# control_board_WS2812.net
KiCad netlist of a schematic drawn in EAGLE
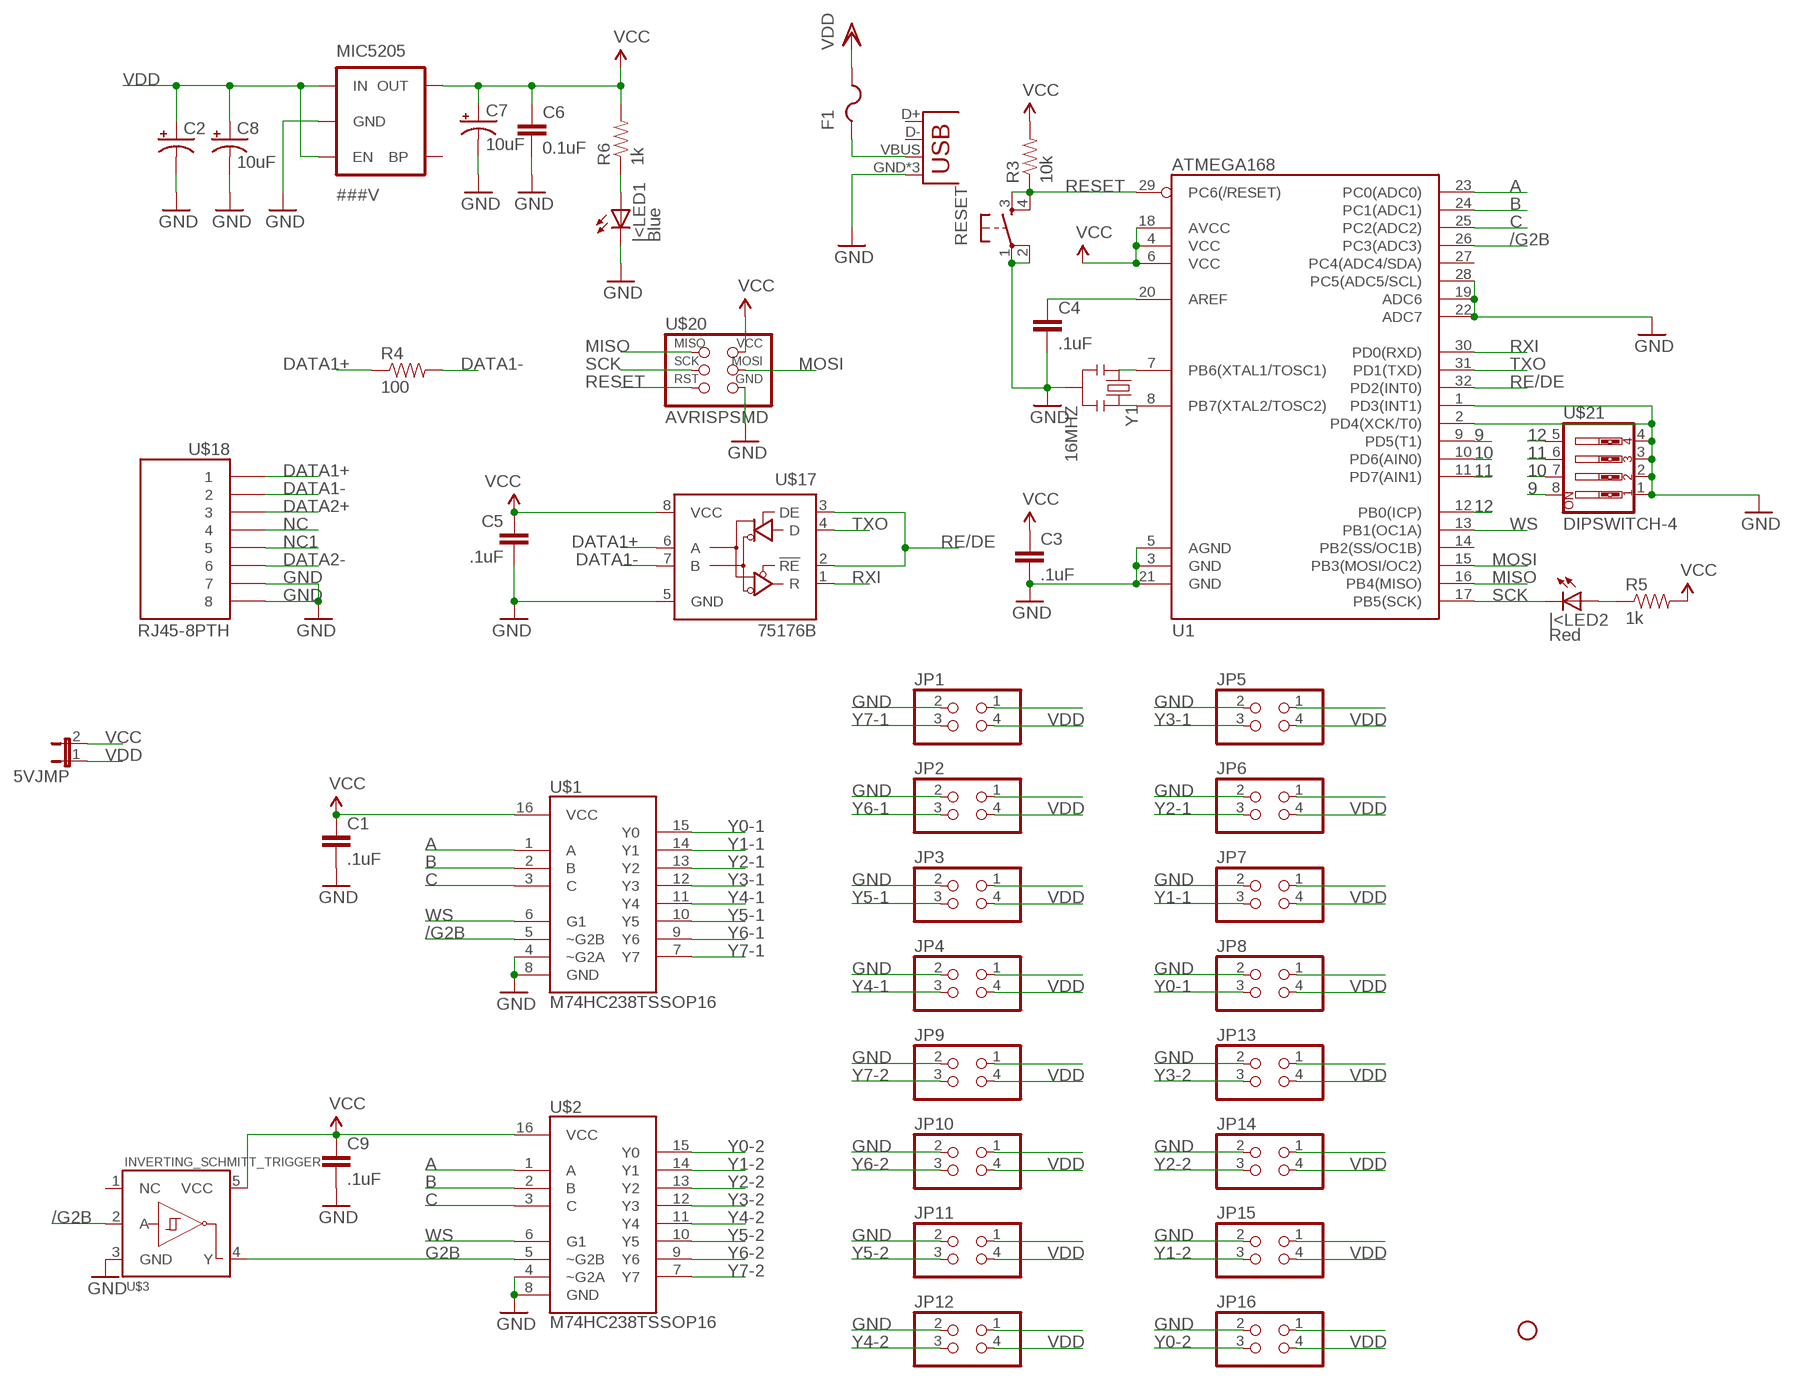
[diagram p0: schematic, sheet 1]

(export (version "E")
  (design (tool "Eeschema 10.0.6"))
  (components
    (comp (ref "5VJMP")
      (value "JUMPER-2SMD-NO")
      (footprint "eagle-import:SJ_2S-NO")
      (libsource (lib "eagle-import") (part "JUMPER-2SMD-NO"))
    )
    (comp (ref "C1")
      (value ".1uF")
      (footprint "eagle-import:0402-CAP")
      (libsource (lib "eagle-import") (part "CAP0402-CAP"))
    )
    (comp (ref "C2")
      (value "CAP_POLC")
      (footprint "eagle-import:PANASONIC_C")
      (libsource (lib "eagle-import") (part "CAP_POLC"))
    )
    (comp (ref "C3")
      (value ".1uF")
      (footprint "eagle-import:0402-CAP")
      (libsource (lib "eagle-import") (part "CAP0402-CAP"))
    )
    (comp (ref "C4")
      (value ".1uF")
      (footprint "eagle-import:0402-CAP")
      (libsource (lib "eagle-import") (part "CAP0402-CAP"))
    )
    (comp (ref "C5")
      (value ".1uF")
      (footprint "eagle-import:0402-CAP")
      (libsource (lib "eagle-import") (part "CAP0402-CAP"))
    )
    (comp (ref "C6")
      (value "0.1uF")
      (footprint "eagle-import:0402-CAP")
      (libsource (lib "eagle-import") (part "CAP0402-CAP"))
    )
    (comp (ref "C7")
      (value "10uF")
      (footprint "eagle-import:EIA3216")
      (libsource (lib "eagle-import") (part "CAP_POL1206"))
    )
    (comp (ref "C8")
      (value "10uF")
      (footprint "eagle-import:EIA3216")
      (libsource (lib "eagle-import") (part "CAP_POL1206"))
    )
    (comp (ref "C9")
      (value ".1uF")
      (footprint "eagle-import:0402-CAP")
      (libsource (lib "eagle-import") (part "CAP0402-CAP"))
    )
    (comp (ref "F1")
      (value "PTCFUSE-1812")
      (footprint "eagle-import:1812")
      (libsource (lib "eagle-import") (part "PTCFUSE-1812"))
    )
    (comp (ref "JP1")
      (value "PINHD-2X2")
      (footprint "eagle-import:2X02")
      (libsource (lib "eagle-import") (part "PINHD-2X2"))
    )
    (comp (ref "JP2")
      (value "PINHD-2X2")
      (footprint "eagle-import:2X02")
      (libsource (lib "eagle-import") (part "PINHD-2X2"))
    )
    (comp (ref "JP3")
      (value "PINHD-2X2")
      (footprint "eagle-import:2X02")
      (libsource (lib "eagle-import") (part "PINHD-2X2"))
    )
    (comp (ref "JP4")
      (value "PINHD-2X2")
      (footprint "eagle-import:2X02")
      (libsource (lib "eagle-import") (part "PINHD-2X2"))
    )
    (comp (ref "JP5")
      (value "PINHD-2X2")
      (footprint "eagle-import:2X02")
      (libsource (lib "eagle-import") (part "PINHD-2X2"))
    )
    (comp (ref "JP6")
      (value "PINHD-2X2")
      (footprint "eagle-import:2X02")
      (libsource (lib "eagle-import") (part "PINHD-2X2"))
    )
    (comp (ref "JP7")
      (value "PINHD-2X2")
      (footprint "eagle-import:2X02")
      (libsource (lib "eagle-import") (part "PINHD-2X2"))
    )
    (comp (ref "JP8")
      (value "PINHD-2X2")
      (footprint "eagle-import:2X02")
      (libsource (lib "eagle-import") (part "PINHD-2X2"))
    )
    (comp (ref "JP9")
      (value "PINHD-2X2")
      (footprint "eagle-import:2X02")
      (libsource (lib "eagle-import") (part "PINHD-2X2"))
    )
    (comp (ref "JP10")
      (value "PINHD-2X2")
      (footprint "eagle-import:2X02")
      (libsource (lib "eagle-import") (part "PINHD-2X2"))
    )
    (comp (ref "JP11")
      (value "PINHD-2X2")
      (footprint "eagle-import:2X02")
      (libsource (lib "eagle-import") (part "PINHD-2X2"))
    )
    (comp (ref "JP12")
      (value "PINHD-2X2")
      (footprint "eagle-import:2X02")
      (libsource (lib "eagle-import") (part "PINHD-2X2"))
    )
    (comp (ref "JP13")
      (value "PINHD-2X2")
      (footprint "eagle-import:2X02")
      (libsource (lib "eagle-import") (part "PINHD-2X2"))
    )
    (comp (ref "JP14")
      (value "PINHD-2X2")
      (footprint "eagle-import:2X02")
      (libsource (lib "eagle-import") (part "PINHD-2X2"))
    )
    (comp (ref "JP15")
      (value "PINHD-2X2")
      (footprint "eagle-import:2X02")
      (libsource (lib "eagle-import") (part "PINHD-2X2"))
    )
    (comp (ref "JP16")
      (value "PINHD-2X2")
      (footprint "eagle-import:2X02")
      (libsource (lib "eagle-import") (part "PINHD-2X2"))
    )
    (comp (ref "JP17")
      (value "USB-MICROB")
      (footprint "eagle-import:USB-MICROB")
      (libsource (lib "eagle-import") (part "USB-MICROB"))
    )
    (comp (ref "MIC5205")
      (value "###V")
      (footprint "eagle-import:SOT23-5")
      (libsource (lib "eagle-import") (part "V_REG_LDOSMD"))
    )
    (comp (ref "R3")
      (value "10k")
      (footprint "eagle-import:0402-RES")
      (libsource (lib "eagle-import") (part "RESISTOR0402-RES"))
    )
    (comp (ref "R4")
      (value "100")
      (footprint "eagle-import:1206")
      (libsource (lib "eagle-import") (part "SparkFun-Passives_RESISTOR1206"))
    )
    (comp (ref "R5")
      (value "1k")
      (footprint "eagle-import:C0402")
      (libsource (lib "eagle-import") (part "RESISTOR0402"))
    )
    (comp (ref "R6")
      (value "1k")
      (footprint "eagle-import:C0402")
      (libsource (lib "eagle-import") (part "RESISTOR0402"))
    )
    (comp (ref "RESET")
      (value "TAC_SWITCHSMD")
      (footprint "eagle-import:TACTILE_SWITCH_SMD")
      (libsource (lib "eagle-import") (part "TAC_SWITCHSMD"))
    )
    (comp (ref "STANDOFF1")
      (value "STAND-OFF")
      (footprint "eagle-import:STAND-OFF")
      (libsource (lib "eagle-import") (part "STAND-OFF"))
    )
    (comp (ref "U$1")
      (value "M74HC238TSSOP16")
      (footprint "eagle-import:TSSOP16")
      (libsource (lib "eagle-import") (part "M74HC238TSSOP16"))
    )
    (comp (ref "U$2")
      (value "M74HC238TSSOP16")
      (footprint "eagle-import:TSSOP16")
      (libsource (lib "eagle-import") (part "M74HC238TSSOP16"))
    )
    (comp (ref "U$3")
      (value "INVERTING_SCHMITT_TRIGGER")
      (footprint "eagle-import:TSSOP5")
      (libsource (lib "eagle-import") (part "INVERTING_SCHMITT_TRIGGER"))
    )
    (comp (ref "U$17")
      (value "75176B")
      (footprint "eagle-import:D_R-PDSO-G8")
      (libsource (lib "eagle-import") (part "75176B"))
    )
    (comp (ref "U$18")
      (value "RJ45-8PTH")
      (footprint "eagle-import:RJ45-8")
      (libsource (lib "eagle-import") (part "RJ45-8PTH"))
    )
    (comp (ref "U$20")
      (value "AVRISPSMD")
      (footprint "eagle-import:2X03SMD")
      (libsource (lib "eagle-import") (part "AVRISPSMD"))
    )
    (comp (ref "U$21")
      (value "DIPSWITCH-4")
      (footprint "eagle-import:DIPSWITCH-04")
      (libsource (lib "eagle-import") (part "DIPSWITCH-4"))
    )
    (comp (ref "U1")
      (value "ATMEGA168")
      (footprint "eagle-import:TQFP32-08")
      (libsource (lib "eagle-import") (part "ATMEGA168"))
    )
    (comp (ref "Y1")
      (value "16MHZ")
      (footprint "eagle-import:RESONATOR-SMD")
      (libsource (lib "eagle-import") (part "RESONATOR8MHZ"))
    )
    (comp (ref "|<LED1")
      (value "Blue")
      (footprint "eagle-import:LED-0603")
      (libsource (lib "eagle-import") (part "LED0603"))
    )
    (comp (ref "|<LED2")
      (value "Red")
      (footprint "eagle-import:LED-0603")
      (libsource (lib "eagle-import") (part "LED0603"))
    )
  )
  (nets
    (net (code "1") (name "/9") (class "Default")
      (node (ref "U$21") (pin "8") (pinfunction "8_8") (pintype "passive"))
      (node (ref "U1") (pin "9") (pinfunction "PD5(T1)_9") (pintype "bidirectional"))
    )
    (net (code "2") (name "/10") (class "Default")
      (node (ref "U$21") (pin "7") (pinfunction "7_7") (pintype "passive"))
      (node (ref "U1") (pin "10") (pinfunction "PD6(AIN0)_10") (pintype "bidirectional"))
    )
    (net (code "3") (name "/11") (class "Default")
      (node (ref "U$21") (pin "6") (pinfunction "6_6") (pintype "passive"))
      (node (ref "U1") (pin "11") (pinfunction "PD7(AIN1)_11") (pintype "bidirectional"))
    )
    (net (code "4") (name "/12") (class "Default")
      (node (ref "U$21") (pin "5") (pinfunction "5_5") (pintype "passive"))
      (node (ref "U1") (pin "12") (pinfunction "PB0(ICP)_12") (pintype "bidirectional"))
    )
    (net (code "5") (name "/A") (class "Default")
      (node (ref "U$1") (pin "1") (pinfunction "A_1") (pintype "bidirectional"))
      (node (ref "U$2") (pin "1") (pinfunction "A_1") (pintype "bidirectional"))
      (node (ref "U1") (pin "23") (pinfunction "PC0(ADC0)_23") (pintype "bidirectional"))
    )
    (net (code "6") (name "/B") (class "Default")
      (node (ref "U$1") (pin "2") (pinfunction "B_2") (pintype "bidirectional"))
      (node (ref "U$2") (pin "2") (pinfunction "B_2") (pintype "bidirectional"))
      (node (ref "U1") (pin "24") (pinfunction "PC1(ADC1)_24") (pintype "bidirectional"))
    )
    (net (code "7") (name "/C") (class "Default")
      (node (ref "U$1") (pin "3") (pinfunction "C_3") (pintype "bidirectional"))
      (node (ref "U$2") (pin "3") (pinfunction "C_3") (pintype "bidirectional"))
      (node (ref "U1") (pin "25") (pinfunction "PC2(ADC2)_25") (pintype "bidirectional"))
    )
    (net (code "8") (name "/DATA1+") (class "Default")
      (node (ref "R4") (pin "1") (pinfunction "1_1") (pintype "passive"))
      (node (ref "U$17") (pin "6") (pinfunction "A_6") (pintype "output"))
      (node (ref "U$18") (pin "1") (pinfunction "1_1") (pintype "bidirectional"))
    )
    (net (code "9") (name "/DATA1-") (class "Default")
      (node (ref "R4") (pin "2") (pinfunction "2_2") (pintype "passive"))
      (node (ref "U$17") (pin "7") (pinfunction "B_7") (pintype "output"))
      (node (ref "U$18") (pin "2") (pinfunction "2_2") (pintype "bidirectional"))
    )
    (net (code "10") (name "/DATA2+") (class "Default")
      (node (ref "U$18") (pin "3") (pinfunction "3_3") (pintype "bidirectional"))
    )
    (net (code "11") (name "/DATA2-") (class "Default")
      (node (ref "U$18") (pin "6") (pinfunction "6_6") (pintype "bidirectional"))
    )
    (net (code "12") (name "/G2B") (class "Default")
      (node (ref "U$2") (pin "5") (pinfunction "~{G2B}_5") (pintype "bidirectional"))
      (node (ref "U$3") (pin "4") (pinfunction "Y_4") (pintype "bidirectional"))
    )
    (net (code "13") (name "/MISO") (class "Default")
      (node (ref "U$20") (pin "1") (pinfunction "MISO_1") (pintype "passive"))
      (node (ref "U1") (pin "16") (pinfunction "PB4(MISO)_16") (pintype "bidirectional"))
    )
    (net (code "14") (name "/MOSI") (class "Default")
      (node (ref "U$20") (pin "4") (pinfunction "MOSI_4") (pintype "passive"))
      (node (ref "U1") (pin "15") (pinfunction "PB3(MOSI/OC2)_15") (pintype "bidirectional"))
    )
    (net (code "15") (name "/NC") (class "Default")
      (node (ref "U$18") (pin "4") (pinfunction "4_4") (pintype "bidirectional"))
    )
    (net (code "16") (name "/NC1") (class "Default")
      (node (ref "U$18") (pin "5") (pinfunction "5_5") (pintype "bidirectional"))
    )
    (net (code "17") (name "/RESET") (class "Default")
      (node (ref "R3") (pin "1") (pinfunction "1_1") (pintype "passive"))
      (node (ref "RESET") (pin "3") (pinfunction "3_3") (pintype "passive"))
      (node (ref "RESET") (pin "4") (pinfunction "4_4") (pintype "passive"))
      (node (ref "U$20") (pin "5") (pinfunction "RST_5") (pintype "passive"))
      (node (ref "U1") (pin "29") (pinfunction "PC6(/RESET)_29") (pintype "bidirectional"))
    )
    (net (code "18") (name "/RE{slash}DE") (class "Default")
      (node (ref "U$17") (pin "2") (pinfunction "~{RE}_2") (pintype "input"))
      (node (ref "U$17") (pin "3") (pinfunction "DE_3") (pintype "input"))
      (node (ref "U1") (pin "32") (pinfunction "PD2(INT0)_32") (pintype "bidirectional"))
    )
    (net (code "19") (name "/RXI") (class "Default")
      (node (ref "U$17") (pin "1") (pinfunction "R_1") (pintype "input"))
      (node (ref "U1") (pin "30") (pinfunction "PD0(RXD)_30") (pintype "bidirectional"))
    )
    (net (code "20") (name "/SCK") (class "Default")
      (node (ref "U$20") (pin "3") (pinfunction "SCK_3") (pintype "passive"))
      (node (ref "U1") (pin "17") (pinfunction "PB5(SCK)_17") (pintype "bidirectional"))
      (node (ref "|<LED2") (pin "C") (pinfunction "C_C") (pintype "passive"))
    )
    (net (code "21") (name "/TXO") (class "Default")
      (node (ref "U$17") (pin "4") (pinfunction "D_4") (pintype "input"))
      (node (ref "U1") (pin "31") (pinfunction "PD1(TXD)_31") (pintype "bidirectional"))
    )
    (net (code "22") (name "/WS") (class "Default")
      (node (ref "U$1") (pin "6") (pinfunction "G1_6") (pintype "bidirectional"))
      (node (ref "U$2") (pin "6") (pinfunction "G1_6") (pintype "bidirectional"))
      (node (ref "U1") (pin "13") (pinfunction "PB1(OC1A)_13") (pintype "bidirectional"))
    )
    (net (code "23") (name "/Y0-1") (class "Default")
      (node (ref "JP8") (pin "3") (pinfunction "3_3") (pintype "passive"))
      (node (ref "U$1") (pin "15") (pinfunction "Y0_15") (pintype "bidirectional"))
    )
    (net (code "24") (name "/Y0-2") (class "Default")
      (node (ref "JP16") (pin "3") (pinfunction "3_3") (pintype "passive"))
      (node (ref "U$2") (pin "15") (pinfunction "Y0_15") (pintype "bidirectional"))
    )
    (net (code "25") (name "/Y1-1") (class "Default")
      (node (ref "JP7") (pin "3") (pinfunction "3_3") (pintype "passive"))
      (node (ref "U$1") (pin "14") (pinfunction "Y1_14") (pintype "bidirectional"))
    )
    (net (code "26") (name "/Y1-2") (class "Default")
      (node (ref "JP15") (pin "3") (pinfunction "3_3") (pintype "passive"))
      (node (ref "U$2") (pin "14") (pinfunction "Y1_14") (pintype "bidirectional"))
    )
    (net (code "27") (name "/Y2-1") (class "Default")
      (node (ref "JP6") (pin "3") (pinfunction "3_3") (pintype "passive"))
      (node (ref "U$1") (pin "13") (pinfunction "Y2_13") (pintype "bidirectional"))
    )
    (net (code "28") (name "/Y2-2") (class "Default")
      (node (ref "JP14") (pin "3") (pinfunction "3_3") (pintype "passive"))
      (node (ref "U$2") (pin "13") (pinfunction "Y2_13") (pintype "bidirectional"))
    )
    (net (code "29") (name "/Y3-1") (class "Default")
      (node (ref "JP5") (pin "3") (pinfunction "3_3") (pintype "passive"))
      (node (ref "U$1") (pin "12") (pinfunction "Y3_12") (pintype "bidirectional"))
    )
    (net (code "30") (name "/Y3-2") (class "Default")
      (node (ref "JP13") (pin "3") (pinfunction "3_3") (pintype "passive"))
      (node (ref "U$2") (pin "12") (pinfunction "Y3_12") (pintype "bidirectional"))
    )
    (net (code "31") (name "/Y4-1") (class "Default")
      (node (ref "JP4") (pin "3") (pinfunction "3_3") (pintype "passive"))
      (node (ref "U$1") (pin "11") (pinfunction "Y4_11") (pintype "bidirectional"))
    )
    (net (code "32") (name "/Y4-2") (class "Default")
      (node (ref "JP12") (pin "3") (pinfunction "3_3") (pintype "passive"))
      (node (ref "U$2") (pin "11") (pinfunction "Y4_11") (pintype "bidirectional"))
    )
    (net (code "33") (name "/Y5-1") (class "Default")
      (node (ref "JP3") (pin "3") (pinfunction "3_3") (pintype "passive"))
      (node (ref "U$1") (pin "10") (pinfunction "Y5_10") (pintype "bidirectional"))
    )
    (net (code "34") (name "/Y5-2") (class "Default")
      (node (ref "JP11") (pin "3") (pinfunction "3_3") (pintype "passive"))
      (node (ref "U$2") (pin "10") (pinfunction "Y5_10") (pintype "bidirectional"))
    )
    (net (code "35") (name "/Y6-1") (class "Default")
      (node (ref "JP2") (pin "3") (pinfunction "3_3") (pintype "passive"))
      (node (ref "U$1") (pin "9") (pinfunction "Y6_9") (pintype "bidirectional"))
    )
    (net (code "36") (name "/Y6-2") (class "Default")
      (node (ref "JP10") (pin "3") (pinfunction "3_3") (pintype "passive"))
      (node (ref "U$2") (pin "9") (pinfunction "Y6_9") (pintype "bidirectional"))
    )
    (net (code "37") (name "/Y7-1") (class "Default")
      (node (ref "JP1") (pin "3") (pinfunction "3_3") (pintype "passive"))
      (node (ref "U$1") (pin "7") (pinfunction "Y7_7") (pintype "bidirectional"))
    )
    (net (code "38") (name "/Y7-2") (class "Default")
      (node (ref "JP9") (pin "3") (pinfunction "3_3") (pintype "passive"))
      (node (ref "U$2") (pin "7") (pinfunction "Y7_7") (pintype "bidirectional"))
    )
    (net (code "39") (name "/{slash}G2B") (class "Default")
      (node (ref "U$1") (pin "5") (pinfunction "~{G2B}_5") (pintype "bidirectional"))
      (node (ref "U$3") (pin "2") (pinfunction "A_2") (pintype "bidirectional"))
      (node (ref "U1") (pin "26") (pinfunction "PC3(ADC3)_26") (pintype "bidirectional"))
    )
    (net (code "40") (name "GND") (class "Default")
      (node (ref "C1") (pin "2") (pinfunction "2_2") (pintype "passive"))
      (node (ref "C2") (pin "-") (pinfunction "-_-") (pintype "passive"))
      (node (ref "C3") (pin "2") (pinfunction "2_2") (pintype "passive"))
      (node (ref "C4") (pin "2") (pinfunction "2_2") (pintype "passive"))
      (node (ref "C5") (pin "2") (pinfunction "2_2") (pintype "passive"))
      (node (ref "C6") (pin "2") (pinfunction "2_2") (pintype "passive"))
      (node (ref "C7") (pin "C") (pinfunction "-_C") (pintype "passive"))
      (node (ref "C8") (pin "C") (pinfunction "-_C") (pintype "passive"))
      (node (ref "C9") (pin "2") (pinfunction "2_2") (pintype "passive"))
      (node (ref "JP1") (pin "2") (pinfunction "2_2") (pintype "passive"))
      (node (ref "JP10") (pin "2") (pinfunction "2_2") (pintype "passive"))
      (node (ref "JP11") (pin "2") (pinfunction "2_2") (pintype "passive"))
      (node (ref "JP12") (pin "2") (pinfunction "2_2") (pintype "passive"))
      (node (ref "JP13") (pin "2") (pinfunction "2_2") (pintype "passive"))
      (node (ref "JP14") (pin "2") (pinfunction "2_2") (pintype "passive"))
      (node (ref "JP15") (pin "2") (pinfunction "2_2") (pintype "passive"))
      (node (ref "JP16") (pin "2") (pinfunction "2_2") (pintype "passive"))
      (node (ref "JP17") (pin "GND") (pinfunction "GND_GND") (pintype "bidirectional"))
      (node (ref "JP17") (pin "MT1") (pinfunction "GND_MT1") (pintype "bidirectional"))
      (node (ref "JP17") (pin "MT2") (pinfunction "GND_MT2") (pintype "bidirectional"))
      (node (ref "JP2") (pin "2") (pinfunction "2_2") (pintype "passive"))
      (node (ref "JP3") (pin "2") (pinfunction "2_2") (pintype "passive"))
      (node (ref "JP4") (pin "2") (pinfunction "2_2") (pintype "passive"))
      (node (ref "JP5") (pin "2") (pinfunction "2_2") (pintype "passive"))
      (node (ref "JP6") (pin "2") (pinfunction "2_2") (pintype "passive"))
      (node (ref "JP7") (pin "2") (pinfunction "2_2") (pintype "passive"))
      (node (ref "JP8") (pin "2") (pinfunction "2_2") (pintype "passive"))
      (node (ref "JP9") (pin "2") (pinfunction "2_2") (pintype "passive"))
      (node (ref "MIC5205") (pin "2") (pinfunction "GND_2") (pintype "input"))
      (node (ref "RESET") (pin "1") (pinfunction "1_1") (pintype "passive"))
      (node (ref "RESET") (pin "2") (pinfunction "2_2") (pintype "passive"))
      (node (ref "U$1") (pin "4") (pinfunction "~{G2A}_4") (pintype "bidirectional"))
      (node (ref "U$1") (pin "8") (pinfunction "GND_8") (pintype "bidirectional"))
      (node (ref "U$17") (pin "5") (pinfunction "GND_5") (pintype "power_in"))
      (node (ref "U$18") (pin "7") (pinfunction "7_7") (pintype "bidirectional"))
      (node (ref "U$18") (pin "8") (pinfunction "8_8") (pintype "bidirectional"))
      (node (ref "U$2") (pin "4") (pinfunction "~{G2A}_4") (pintype "bidirectional"))
      (node (ref "U$2") (pin "8") (pinfunction "GND_8") (pintype "bidirectional"))
      (node (ref "U$20") (pin "6") (pinfunction "GND_6") (pintype "passive"))
      (node (ref "U$21") (pin "1") (pinfunction "1_1") (pintype "passive"))
      (node (ref "U$21") (pin "2") (pinfunction "2_2") (pintype "passive"))
      (node (ref "U$21") (pin "3") (pinfunction "3_3") (pintype "passive"))
      (node (ref "U$21") (pin "4") (pinfunction "4_4") (pintype "passive"))
      (node (ref "U$3") (pin "3") (pinfunction "GND_3") (pintype "bidirectional"))
      (node (ref "U1") (pin "1") (pinfunction "PD3(INT1)_1") (pintype "bidirectional"))
      (node (ref "U1") (pin "19") (pinfunction "ADC6_19") (pintype "bidirectional"))
      (node (ref "U1") (pin "2") (pinfunction "PD4(XCK/T0)_2") (pintype "bidirectional"))
      (node (ref "U1") (pin "21") (pinfunction "GND_21") (pintype "bidirectional"))
      (node (ref "U1") (pin "22") (pinfunction "ADC7_22") (pintype "bidirectional"))
      (node (ref "U1") (pin "28") (pinfunction "PC5(ADC5/SCL)_28") (pintype "bidirectional"))
      (node (ref "U1") (pin "3") (pinfunction "GND_3") (pintype "bidirectional"))
      (node (ref "U1") (pin "5") (pinfunction "AGND_5") (pintype "bidirectional"))
      (node (ref "Y1") (pin "2") (pinfunction "2_2") (pintype "passive"))
      (node (ref "|<LED1") (pin "C") (pinfunction "C_C") (pintype "passive"))
    )
    (net (code "41") (name "Net-(F1-Pad1)") (class "Default")
      (node (ref "F1") (pin "1") (pinfunction "1_1") (pintype "passive"))
      (node (ref "JP17") (pin "VBUS") (pinfunction "VBUS_VBUS") (pintype "bidirectional"))
    )
    (net (code "42") (name "Net-(R5-Pad1)") (class "Default")
      (node (ref "R5") (pin "1") (pinfunction "1_1") (pintype "passive"))
      (node (ref "|<LED2") (pin "A") (pinfunction "A_A") (pintype "passive"))
    )
    (net (code "43") (name "Net-(R6-Pad1)") (class "Default")
      (node (ref "R6") (pin "1") (pinfunction "1_1") (pintype "passive"))
      (node (ref "|<LED1") (pin "A") (pinfunction "A_A") (pintype "passive"))
    )
    (net (code "44") (name "Net-(U1-AREF)") (class "Default")
      (node (ref "C4") (pin "1") (pinfunction "1_1") (pintype "passive"))
      (node (ref "U1") (pin "20") (pinfunction "AREF_20") (pintype "bidirectional"))
    )
    (net (code "45") (name "Net-(U1-PB6(XTAL1{slash}TOSC1))") (class "Default")
      (node (ref "U1") (pin "7") (pinfunction "PB6(XTAL1/TOSC1)_7") (pintype "bidirectional"))
      (node (ref "Y1") (pin "1") (pinfunction "1_1") (pintype "passive"))
    )
    (net (code "46") (name "Net-(U1-PB7(XTAL2{slash}TOSC2))") (class "Default")
      (node (ref "U1") (pin "8") (pinfunction "PB7(XTAL2/TOSC2)_8") (pintype "bidirectional"))
      (node (ref "Y1") (pin "3") (pinfunction "3_3") (pintype "passive"))
    )
    (net (code "47") (name "VCC") (class "Default")
      (node (ref "5VJMP") (pin "2") (pinfunction "2_2") (pintype "passive"))
      (node (ref "C1") (pin "1") (pinfunction "1_1") (pintype "passive"))
      (node (ref "C3") (pin "1") (pinfunction "1_1") (pintype "passive"))
      (node (ref "C5") (pin "1") (pinfunction "1_1") (pintype "passive"))
      (node (ref "C6") (pin "1") (pinfunction "1_1") (pintype "passive"))
      (node (ref "C7") (pin "A") (pinfunction "+_A") (pintype "passive"))
      (node (ref "C9") (pin "1") (pinfunction "1_1") (pintype "passive"))
      (node (ref "MIC5205") (pin "5") (pinfunction "OUT_5") (pintype "passive"))
      (node (ref "R3") (pin "2") (pinfunction "2_2") (pintype "passive"))
      (node (ref "R5") (pin "2") (pinfunction "2_2") (pintype "passive"))
      (node (ref "R6") (pin "2") (pinfunction "2_2") (pintype "passive"))
      (node (ref "U$1") (pin "16") (pinfunction "VCC_16") (pintype "bidirectional"))
      (node (ref "U$17") (pin "8") (pinfunction "VCC_8") (pintype "power_in"))
      (node (ref "U$2") (pin "16") (pinfunction "VCC_16") (pintype "bidirectional"))
      (node (ref "U$20") (pin "2") (pinfunction "VCC_2") (pintype "passive"))
      (node (ref "U$3") (pin "5") (pinfunction "VCC_5") (pintype "bidirectional"))
      (node (ref "U1") (pin "18") (pinfunction "AVCC_18") (pintype "bidirectional"))
      (node (ref "U1") (pin "4") (pinfunction "VCC_4") (pintype "bidirectional"))
      (node (ref "U1") (pin "6") (pinfunction "VCC_6") (pintype "bidirectional"))
    )
    (net (code "48") (name "VDD") (class "Default")
      (node (ref "5VJMP") (pin "1") (pinfunction "1_1") (pintype "passive"))
      (node (ref "C2") (pin "+") (pinfunction "+_+") (pintype "passive"))
      (node (ref "C8") (pin "A") (pinfunction "+_A") (pintype "passive"))
      (node (ref "F1") (pin "2") (pinfunction "2_2") (pintype "passive"))
      (node (ref "JP1") (pin "4") (pinfunction "4_4") (pintype "passive"))
      (node (ref "JP10") (pin "4") (pinfunction "4_4") (pintype "passive"))
      (node (ref "JP11") (pin "4") (pinfunction "4_4") (pintype "passive"))
      (node (ref "JP12") (pin "4") (pinfunction "4_4") (pintype "passive"))
      (node (ref "JP13") (pin "4") (pinfunction "4_4") (pintype "passive"))
      (node (ref "JP14") (pin "4") (pinfunction "4_4") (pintype "passive"))
      (node (ref "JP15") (pin "4") (pinfunction "4_4") (pintype "passive"))
      (node (ref "JP16") (pin "4") (pinfunction "4_4") (pintype "passive"))
      (node (ref "JP2") (pin "4") (pinfunction "4_4") (pintype "passive"))
      (node (ref "JP3") (pin "4") (pinfunction "4_4") (pintype "passive"))
      (node (ref "JP4") (pin "4") (pinfunction "4_4") (pintype "passive"))
      (node (ref "JP5") (pin "4") (pinfunction "4_4") (pintype "passive"))
      (node (ref "JP6") (pin "4") (pinfunction "4_4") (pintype "passive"))
      (node (ref "JP7") (pin "4") (pinfunction "4_4") (pintype "passive"))
      (node (ref "JP8") (pin "4") (pinfunction "4_4") (pintype "passive"))
      (node (ref "JP9") (pin "4") (pinfunction "4_4") (pintype "passive"))
      (node (ref "MIC5205") (pin "1") (pinfunction "IN_1") (pintype "input"))
      (node (ref "MIC5205") (pin "3") (pinfunction "EN_3") (pintype "input"))
    )
    (net (code "49") (name "unconnected-(JP1-Pad1)") (class "Default")
      (node (ref "JP1") (pin "1") (pinfunction "1_1") (pintype "passive"))
    )
    (net (code "50") (name "unconnected-(JP2-Pad1)") (class "Default")
      (node (ref "JP2") (pin "1") (pinfunction "1_1") (pintype "passive"))
    )
    (net (code "51") (name "unconnected-(JP3-Pad1)") (class "Default")
      (node (ref "JP3") (pin "1") (pinfunction "1_1") (pintype "passive"))
    )
    (net (code "52") (name "unconnected-(JP4-Pad1)") (class "Default")
      (node (ref "JP4") (pin "1") (pinfunction "1_1") (pintype "passive"))
    )
    (net (code "53") (name "unconnected-(JP5-Pad1)") (class "Default")
      (node (ref "JP5") (pin "1") (pinfunction "1_1") (pintype "passive"))
    )
    (net (code "54") (name "unconnected-(JP6-Pad1)") (class "Default")
      (node (ref "JP6") (pin "1") (pinfunction "1_1") (pintype "passive"))
    )
    (net (code "55") (name "unconnected-(JP7-Pad1)") (class "Default")
      (node (ref "JP7") (pin "1") (pinfunction "1_1") (pintype "passive"))
    )
    (net (code "56") (name "unconnected-(JP8-Pad1)") (class "Default")
      (node (ref "JP8") (pin "1") (pinfunction "1_1") (pintype "passive"))
    )
    (net (code "57") (name "unconnected-(JP9-Pad1)") (class "Default")
      (node (ref "JP9") (pin "1") (pinfunction "1_1") (pintype "passive"))
    )
    (net (code "58") (name "unconnected-(JP10-Pad1)") (class "Default")
      (node (ref "JP10") (pin "1") (pinfunction "1_1") (pintype "passive"))
    )
    (net (code "59") (name "unconnected-(JP11-Pad1)") (class "Default")
      (node (ref "JP11") (pin "1") (pinfunction "1_1") (pintype "passive"))
    )
    (net (code "60") (name "unconnected-(JP12-Pad1)") (class "Default")
      (node (ref "JP12") (pin "1") (pinfunction "1_1") (pintype "passive"))
    )
    (net (code "61") (name "unconnected-(JP13-Pad1)") (class "Default")
      (node (ref "JP13") (pin "1") (pinfunction "1_1") (pintype "passive"))
    )
    (net (code "62") (name "unconnected-(JP14-Pad1)") (class "Default")
      (node (ref "JP14") (pin "1") (pinfunction "1_1") (pintype "passive"))
    )
    (net (code "63") (name "unconnected-(JP15-Pad1)") (class "Default")
      (node (ref "JP15") (pin "1") (pinfunction "1_1") (pintype "passive"))
    )
    (net (code "64") (name "unconnected-(JP16-Pad1)") (class "Default")
      (node (ref "JP16") (pin "1") (pinfunction "1_1") (pintype "passive"))
    )
    (net (code "65") (name "unconnected-(JP17-PadD+)") (class "Default")
      (node (ref "JP17") (pin "D+") (pinfunction "D+_D+") (pintype "bidirectional"))
    )
    (net (code "66") (name "unconnected-(JP17-PadD-)") (class "Default")
      (node (ref "JP17") (pin "D-") (pinfunction "D-_D-") (pintype "bidirectional"))
    )
    (net (code "67") (name "unconnected-(MIC5205-BP-Pad4)") (class "Default")
      (node (ref "MIC5205") (pin "4") (pinfunction "BP_4") (pintype "input"))
    )
    (net (code "68") (name "unconnected-(U$3-NC-Pad1)") (class "Default")
      (node (ref "U$3") (pin "1") (pinfunction "NC_1") (pintype "bidirectional"))
    )
    (net (code "69") (name "unconnected-(U1-PB2(SS{slash}OC1B)-Pad14)") (class "Default")
      (node (ref "U1") (pin "14") (pinfunction "PB2(SS/OC1B)_14") (pintype "bidirectional"))
    )
    (net (code "70") (name "unconnected-(U1-PC4(ADC4{slash}SDA)-Pad27)") (class "Default")
      (node (ref "U1") (pin "27") (pinfunction "PC4(ADC4/SDA)_27") (pintype "bidirectional"))
    )
  )
)
